# Connector_Section.net
KiCad netlist of a schematic drawn in Altium Designer
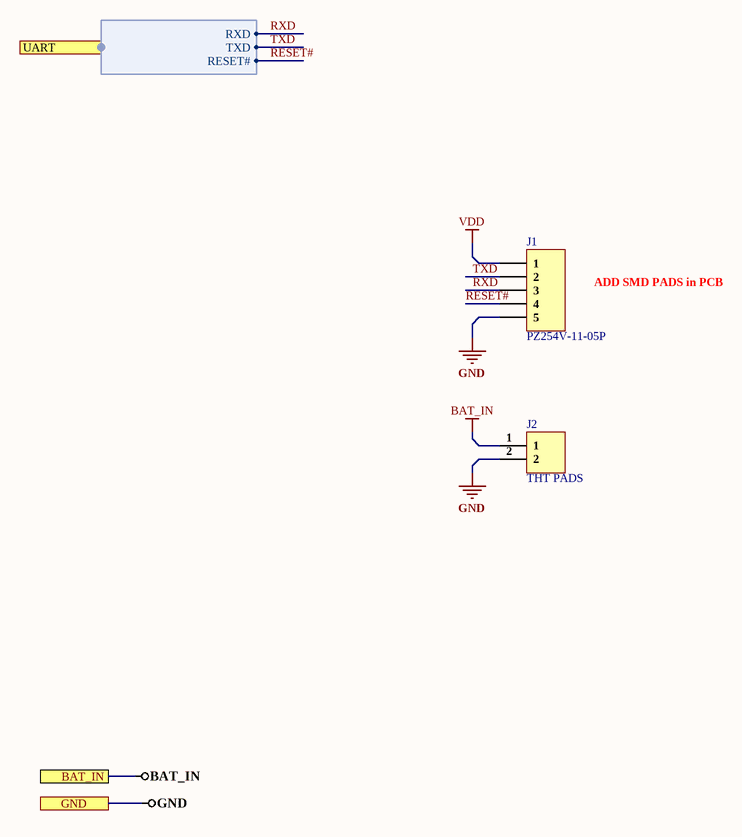
[diagram p0: Connector Section.SchDoc]

(export (version "E")
  (design (tool "Eeschema 10.0.6"))
  (components
    (comp (ref "J1")
      (value "PZ254V-11-05P")
      (footprint "PZ254V-11-05P")
      (description "Pin Header 5 1 right-angle")
      (fields (field (name "MANUFACTURER") "XFCN"))
      (libsource (lib "TT_IntLib") (part "PZ254V-11-05P"))
    )
    (comp (ref "J2") (value "THT PADS") (footprint "THT PAD") (libsource (lib "TT_IntLib") (part "THT PAD")))
  )
  (nets
    (net (code "2") (name "/RESET#") (class "Default")
      (node (ref "J1") (pin "4") (pinfunction "4_4") (pintype "passive"))
    )
    (net (code "3") (name "/RXD") (class "Default")
      (node (ref "J1") (pin "3") (pinfunction "3_3") (pintype "passive"))
    )
    (net (code "4") (name "/TXD") (class "Default")
      (node (ref "J1") (pin "2") (pinfunction "2_2") (pintype "passive"))
    )
    (net (code "6") (name "BAT_IN") (class "Default")
      (node (ref "J2") (pin "1") (pinfunction "1_1") (pintype "passive"))
    )
    (net (code "7") (name "GND") (class "Default")
      (node (ref "J1") (pin "5") (pinfunction "5_5") (pintype "passive"))
      (node (ref "J2") (pin "2") (pinfunction "2_2") (pintype "passive"))
    )
    (net (code "8") (name "VDD") (class "Default")
      (node (ref "J1") (pin "1") (pinfunction "1_1") (pintype "passive"))
    )
  )
)
